# power.net
KiCad netlist of a schematic drawn in Altium Designer
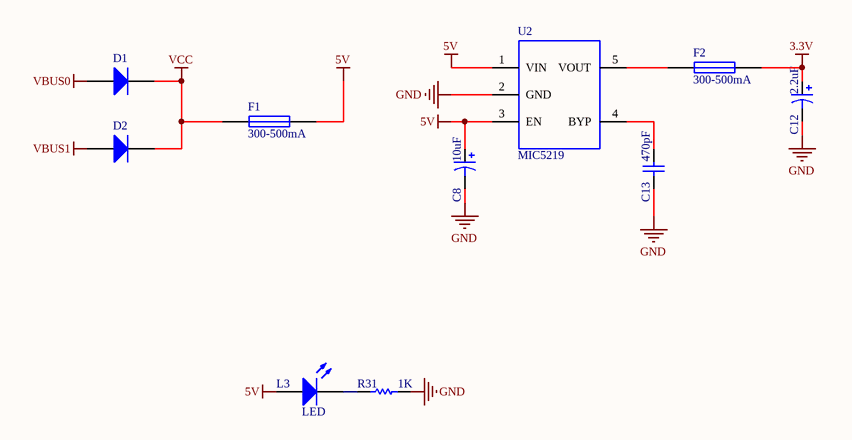
[diagram p0: power.SchDoc]

(export (version "E")
  (design (tool "Eeschema 10.0.6"))
  (components
    (comp (ref "C8")
      (value "10uF")
      (footprint "1206(2)")
      (description "Polarized Capacitor (Radial)")
      (fields (field (name "Comment") "Cap Pol1") (field (name "PUBLISHER") "Altium Limited"))
      (libsource (lib "Miscellaneous Devices") (part "Cap Pol1"))
    )
    (comp (ref "C12")
      (value "2.2uF")
      (footprint "1206(2)")
      (description "Polarized Capacitor (Radial)")
      (fields (field (name "Comment") "Cap Pol1") (field (name "PUBLISHER") "Altium Limited"))
      (libsource (lib "Miscellaneous Devices") (part "Cap Pol1"))
    )
    (comp (ref "C13")
      (value "470pF")
      (footprint "1608[0603]")
      (description "贴片电容")
      (fields (field (name "Comment") "Cap") (field (name "PUBLISHER") "Altium Limited"))
      (libsource (lib "Sparks") (part "Cap"))
    )
    (comp (ref "D1")
      (value "sk4")
      (footprint "1206(2)")
      (description "1 Amp General Purpose Rectifier")
      (fields (field (name "PUBLISHER") "Altium Limited"))
      (libsource (lib "Miscellaneous Devices") (part "Diode 1N4001"))
    )
    (comp (ref "D2")
      (value "sk4")
      (footprint "1206(2)")
      (description "1 Amp General Purpose Rectifier")
      (fields (field (name "PUBLISHER") "Altium Limited"))
      (libsource (lib "Miscellaneous Devices") (part "Diode 1N4001"))
    )
    (comp (ref "F1")
      (value "300-500mA")
      (footprint "1206(2)")
      (description "Fuse")
      (fields (field (name "PUBLISHER") "Altium Limited"))
      (libsource (lib "K60-V4.0") (part "Fuse 1"))
    )
    (comp (ref "F2")
      (value "300-500mA")
      (footprint "1206(2)")
      (description "Fuse")
      (fields (field (name "PUBLISHER") "Altium Limited"))
      (libsource (lib "K60-V4.0") (part "Fuse 1"))
    )
    (comp (ref "L3") (value "LED") (footprint "1608[0603]") (libsource (lib "Sparks") (part "LED")))
    (comp (ref "R31")
      (value "1K")
      (footprint "1608[0603]")
      (description "贴片电阻")
      (fields (field (name "Comment") "Res") (field (name "PUBLISHER") "Altium Limited"))
      (libsource (lib "Sparks") (part "Res"))
    )
    (comp (ref "U2")
      (value "MIC5219")
      (footprint "SOT-23-5")
      (description "LDO")
      (libsource (lib "K60-V4.0") (part "MIC5219"))
    )
  )
  (nets
    (net (code "1") (name "3.3V") (class "Default")
      (node (ref "C12") (pin "1") (pinfunction "1_1") (pintype "passive"))
      (node (ref "F2") (pin "2") (pinfunction "2_2") (pintype "passive"))
    )
    (net (code "2") (name "5V") (class "Default")
      (node (ref "C8") (pin "1") (pinfunction "1_1") (pintype "passive"))
      (node (ref "F1") (pin "2") (pinfunction "2_2") (pintype "passive"))
      (node (ref "L3") (pin "1") (pinfunction "A_1") (pintype "passive"))
      (node (ref "U2") (pin "1") (pinfunction "VIN_1") (pintype "passive"))
      (node (ref "U2") (pin "3") (pinfunction "EN_3") (pintype "passive"))
    )
    (net (code "3") (name "GND") (class "Default")
      (node (ref "C12") (pin "2") (pinfunction "2_2") (pintype "passive"))
      (node (ref "C13") (pin "1") (pinfunction "1_1") (pintype "passive"))
      (node (ref "C8") (pin "2") (pinfunction "2_2") (pintype "passive"))
      (node (ref "R31") (pin "1") (pinfunction "1_1") (pintype "passive"))
      (node (ref "U2") (pin "2") (pinfunction "GND_2") (pintype "passive"))
    )
    (net (code "4") (name "Net-(L3-K)") (class "Default")
      (node (ref "L3") (pin "2") (pinfunction "K_2") (pintype "passive"))
      (node (ref "R31") (pin "2") (pinfunction "2_2") (pintype "passive"))
    )
    (net (code "5") (name "Net-(U2-BYP)") (class "Default")
      (node (ref "C13") (pin "2") (pinfunction "2_2") (pintype "passive"))
      (node (ref "U2") (pin "4") (pinfunction "BYP_4") (pintype "passive"))
    )
    (net (code "6") (name "Net-(U2-VOUT)") (class "Default")
      (node (ref "F2") (pin "1") (pinfunction "1_1") (pintype "passive"))
      (node (ref "U2") (pin "5") (pinfunction "VOUT_5") (pintype "passive"))
    )
    (net (code "7") (name "VBUS0") (class "Default")
      (node (ref "D1") (pin "1") (pinfunction "A_1") (pintype "passive"))
    )
    (net (code "8") (name "VBUS1") (class "Default")
      (node (ref "D2") (pin "1") (pinfunction "A_1") (pintype "passive"))
    )
    (net (code "9") (name "VCC") (class "Default")
      (node (ref "D1") (pin "2") (pinfunction "K_2") (pintype "passive"))
      (node (ref "D2") (pin "2") (pinfunction "K_2") (pintype "passive"))
      (node (ref "F1") (pin "1") (pinfunction "1_1") (pintype "passive"))
    )
  )
)
